# SmartCoffee.net
KiCad netlist of a schematic drawn in EAGLE
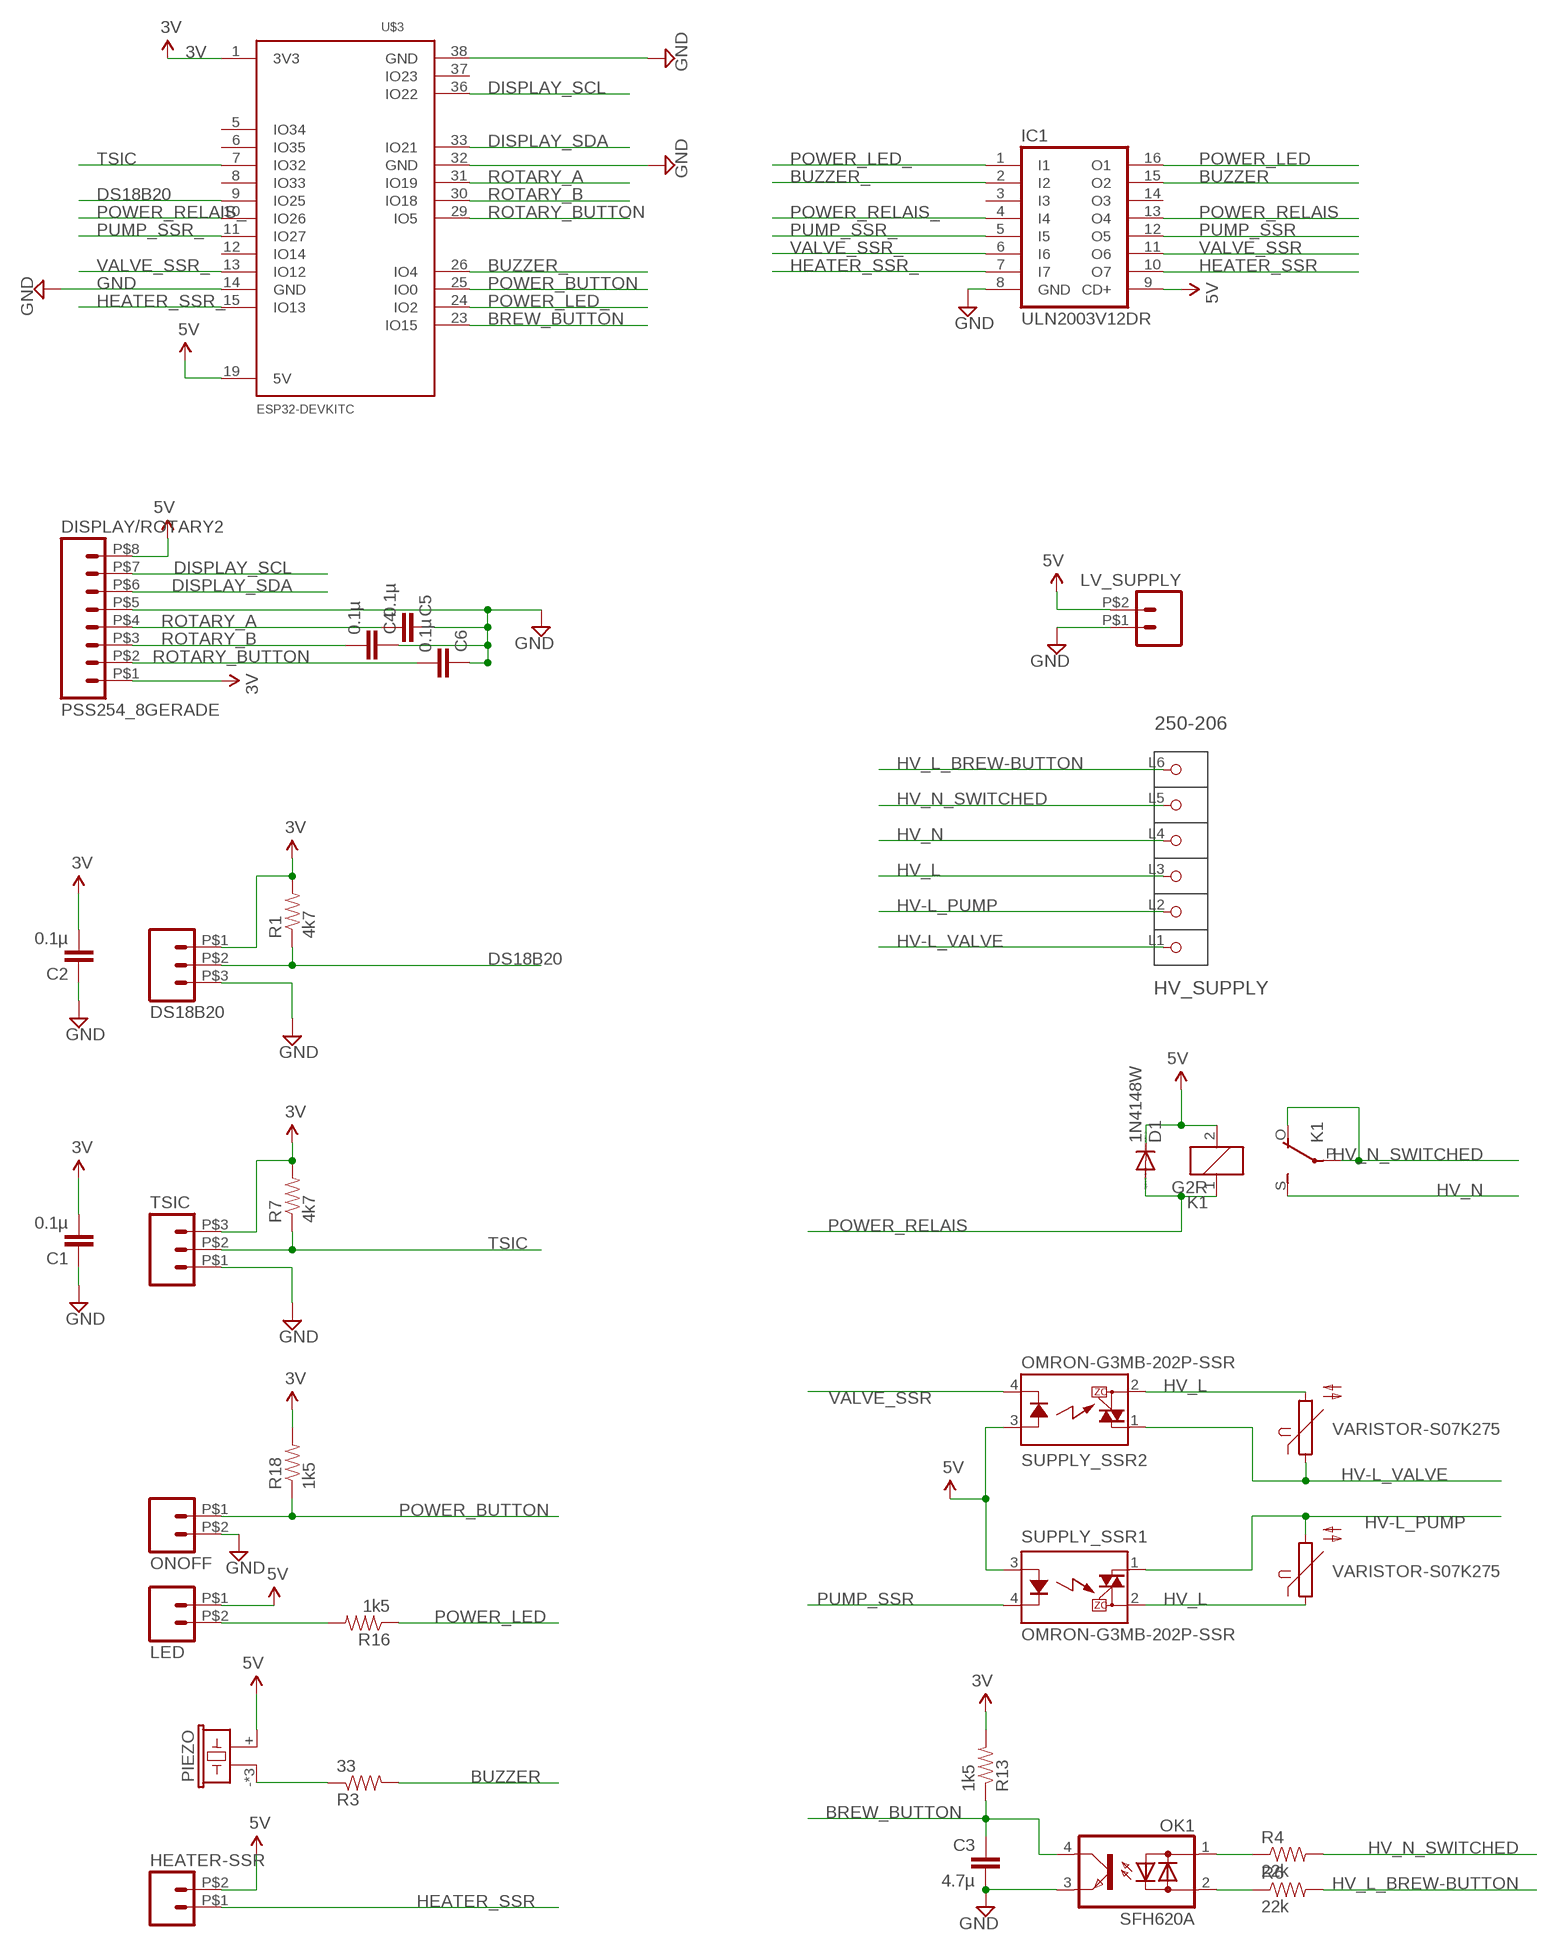
[diagram p0: schematic, sheet 1]

(export (version "E")
  (design (tool "Eeschema 10.0.6"))
  (components
    (comp (ref "C1")
      (value "0.1µ")
      (footprint "eagle-import:0603-CAP")
      (libsource (lib "eagle-import") (part "CAP0603-CAP"))
    )
    (comp (ref "C2")
      (value "0.1µ")
      (footprint "eagle-import:0603-CAP")
      (libsource (lib "eagle-import") (part "CAP0603-CAP"))
    )
    (comp (ref "C3")
      (value "4.7µ")
      (footprint "eagle-import:0805-CAP")
      (libsource (lib "eagle-import") (part "myLib_CAP0805-CAP"))
    )
    (comp (ref "C4")
      (value "0.1µ")
      (footprint "eagle-import:0603-CAP")
      (libsource (lib "eagle-import") (part "CAP0603-CAP"))
    )
    (comp (ref "C5")
      (value "0.1µ")
      (footprint "eagle-import:0603-CAP")
      (libsource (lib "eagle-import") (part "CAP0603-CAP"))
    )
    (comp (ref "C6")
      (value "0.1µ")
      (footprint "eagle-import:0603-CAP")
      (libsource (lib "eagle-import") (part "CAP0603-CAP"))
    )
    (comp (ref "D1")
      (value "1N4148W")
      (footprint "eagle-import:SOD123")
      (libsource (lib "eagle-import") (part "DIODE-SOD123"))
    )
    (comp (ref "DISPLAY/ROTARY2")
      (value "PSS254_8GERADE")
      (footprint "eagle-import:08G")
      (libsource (lib "eagle-import") (part "PSS254_8GERADE"))
    )
    (comp (ref "DS18B20")
      (value "PSS254_3GERADE")
      (footprint "eagle-import:03G")
      (libsource (lib "eagle-import") (part "PSS254_3GERADE"))
    )
    (comp (ref "HEATER-SSR")
      (value "PSS254_2GERADE")
      (footprint "eagle-import:02G")
      (libsource (lib "eagle-import") (part "PSS254_2GERADE"))
    )
    (comp (ref "HV_SUPPLY")
      (value "250-206")
      (footprint "eagle-import:P-250-206")
      (libsource (lib "eagle-import") (part "250-206"))
    )
    (comp (ref "IC1")
      (value "ULN2003V12DR")
      (footprint "eagle-import:SO16")
      (libsource (lib "eagle-import") (part "ULN2003AD"))
    )
    (comp (ref "K1")
      (value "G2R")
      (footprint "eagle-import:G2R")
      (libsource (lib "eagle-import") (part "G2R"))
    )
    (comp (ref "LED")
      (value "PSS254_2GERADE")
      (footprint "eagle-import:02G")
      (libsource (lib "eagle-import") (part "PSS254_2GERADE"))
    )
    (comp (ref "LV_SUPPLY")
      (value "PSS254_2GERADE")
      (footprint "eagle-import:02G")
      (libsource (lib "eagle-import") (part "PSS254_2GERADE"))
    )
    (comp (ref "OK1")
      (value "SFH620A")
      (footprint "eagle-import:DIL04")
      (fields (field (name "MPN") "SFH620A-2"))
      (libsource (lib "eagle-import") (part "SFH620A"))
    )
    (comp (ref "ONOFF")
      (value "PSS254_2GERADE")
      (footprint "eagle-import:02G")
      (libsource (lib "eagle-import") (part "PSS254_2GERADE"))
    )
    (comp (ref "PIEZO")
      (value "BUZZER-PIEZO_SMD")
      (footprint "eagle-import:BUZZER-PIEZO_SMD")
      (libsource (lib "eagle-import") (part "BUZZER-PIEZO_SMD"))
    )
    (comp (ref "R1")
      (value "4k7")
      (footprint "eagle-import:0603-RES")
      (libsource (lib "eagle-import") (part "RESISTOR0603-RES"))
    )
    (comp (ref "R3")
      (value "33")
      (footprint "eagle-import:0603-RES")
      (libsource (lib "eagle-import") (part "RESISTOR0603-RES"))
    )
    (comp (ref "R4")
      (value "22k")
      (footprint "eagle-import:RES_UPRIGHT")
      (libsource (lib "eagle-import") (part "myLib_RESISTORUPRIGHT"))
    )
    (comp (ref "R5")
      (value "VARISTOR-S07K275")
      (footprint "eagle-import:S07K275")
      (libsource (lib "eagle-import") (part "VARISTOR-S07K275"))
    )
    (comp (ref "R6")
      (value "22k")
      (footprint "eagle-import:RES_UPRIGHT")
      (libsource (lib "eagle-import") (part "myLib_RESISTORUPRIGHT"))
    )
    (comp (ref "R7")
      (value "4k7")
      (footprint "eagle-import:0603-RES")
      (libsource (lib "eagle-import") (part "RESISTOR0603-RES"))
    )
    (comp (ref "R8")
      (value "VARISTOR-S07K275")
      (footprint "eagle-import:S07K275")
      (libsource (lib "eagle-import") (part "VARISTOR-S07K275"))
    )
    (comp (ref "R13")
      (value "1k5")
      (footprint "eagle-import:0603-RES")
      (libsource (lib "eagle-import") (part "RESISTOR0603-RES"))
    )
    (comp (ref "R16")
      (value "1k5")
      (footprint "eagle-import:0603-RES")
      (libsource (lib "eagle-import") (part "RESISTOR0603-RES"))
    )
    (comp (ref "R18")
      (value "1k5")
      (footprint "eagle-import:0603-RES")
      (libsource (lib "eagle-import") (part "RESISTOR0603-RES"))
    )
    (comp (ref "SUPPLY_SSR1")
      (value "OMRON-G3MB-202P-SSR")
      (footprint "eagle-import:OMRON-G3MB-202P-SSR")
      (libsource (lib "eagle-import") (part "OMRON-G3MB-202P-SSR"))
    )
    (comp (ref "SUPPLY_SSR2")
      (value "OMRON-G3MB-202P-SSR")
      (footprint "eagle-import:OMRON-G3MB-202P-SSR")
      (libsource (lib "eagle-import") (part "OMRON-G3MB-202P-SSR"))
    )
    (comp (ref "TSIC")
      (value "PSS254_3GERADE")
      (footprint "eagle-import:03G")
      (libsource (lib "eagle-import") (part "PSS254_3GERADE"))
    )
    (comp (ref "U$3")
      (value "ESP32DEVKITC")
      (footprint "eagle-import:ESP32-DEVKITC")
      (libsource (lib "eagle-import") (part "ESP32DEVKITC"))
    )
  )
  (nets
    (net (code "1") (name "/BREW_BUTTON") (class "Default")
      (node (ref "C3") (pin "1") (pinfunction "1_1") (pintype "passive"))
      (node (ref "OK1") (pin "4") (pinfunction "C_4") (pintype "passive"))
      (node (ref "R13") (pin "1") (pinfunction "1_1") (pintype "passive"))
      (node (ref "U$3") (pin "23") (pinfunction "IO15_23") (pintype "bidirectional"))
    )
    (net (code "2") (name "/BUZZER") (class "Default")
      (node (ref "IC1") (pin "15") (pinfunction "O2_15") (pintype "open_collector"))
      (node (ref "R3") (pin "2") (pinfunction "2_2") (pintype "passive"))
    )
    (net (code "3") (name "/BUZZER_") (class "Default")
      (node (ref "IC1") (pin "2") (pinfunction "I2_2") (pintype "input"))
      (node (ref "U$3") (pin "26") (pinfunction "IO4_26") (pintype "bidirectional"))
    )
    (net (code "4") (name "/DISPLAY_SCL") (class "Default")
      (node (ref "DISPLAY/ROTARY2") (pin "P$7") (pinfunction "7_P$7") (pintype "passive"))
      (node (ref "U$3") (pin "36") (pinfunction "IO22_36") (pintype "bidirectional"))
    )
    (net (code "5") (name "/DISPLAY_SDA") (class "Default")
      (node (ref "DISPLAY/ROTARY2") (pin "P$6") (pinfunction "6_P$6") (pintype "passive"))
      (node (ref "U$3") (pin "33") (pinfunction "IO21_33") (pintype "bidirectional"))
    )
    (net (code "6") (name "/DS18B20") (class "Default")
      (node (ref "DS18B20") (pin "P$2") (pinfunction "2_P$2") (pintype "passive"))
      (node (ref "R1") (pin "1") (pinfunction "1_1") (pintype "passive"))
      (node (ref "U$3") (pin "9") (pinfunction "IO25_9") (pintype "bidirectional"))
    )
    (net (code "7") (name "/HEATER_SSR") (class "Default")
      (node (ref "HEATER-SSR") (pin "P$1") (pinfunction "1_P$1") (pintype "passive"))
      (node (ref "IC1") (pin "10") (pinfunction "O7_10") (pintype "open_collector"))
    )
    (net (code "8") (name "/HEATER_SSR_") (class "Default")
      (node (ref "IC1") (pin "7") (pinfunction "I7_7") (pintype "input"))
      (node (ref "U$3") (pin "15") (pinfunction "IO13_15") (pintype "bidirectional"))
    )
    (net (code "9") (name "/HV-L_PUMP") (class "Default")
      (node (ref "HV_SUPPLY") (pin "L2") (pinfunction "P2_L2") (pintype "bidirectional"))
      (node (ref "R8") (pin "2") (pinfunction "2_2") (pintype "passive"))
      (node (ref "SUPPLY_SSR1") (pin "1") (pinfunction "DS1_1") (pintype "passive"))
    )
    (net (code "10") (name "/HV-L_VALVE") (class "Default")
      (node (ref "HV_SUPPLY") (pin "L1") (pinfunction "P1_L1") (pintype "bidirectional"))
      (node (ref "R5") (pin "1") (pinfunction "1_1") (pintype "passive"))
      (node (ref "SUPPLY_SSR2") (pin "1") (pinfunction "DS1_1") (pintype "passive"))
    )
    (net (code "11") (name "/HV_L") (class "Default")
      (node (ref "HV_SUPPLY") (pin "L3") (pinfunction "P3_L3") (pintype "bidirectional"))
      (node (ref "R5") (pin "2") (pinfunction "2_2") (pintype "passive"))
      (node (ref "R8") (pin "1") (pinfunction "1_1") (pintype "passive"))
      (node (ref "SUPPLY_SSR1") (pin "2") (pinfunction "DS2_2") (pintype "passive"))
      (node (ref "SUPPLY_SSR2") (pin "2") (pinfunction "DS2_2") (pintype "passive"))
    )
    (net (code "12") (name "/HV_L_BREW-BUTTON") (class "Default")
      (node (ref "HV_SUPPLY") (pin "L6") (pinfunction "P6_L6") (pintype "bidirectional"))
      (node (ref "R6") (pin "2") (pinfunction "2_2") (pintype "passive"))
    )
    (net (code "13") (name "/HV_N") (class "Default")
      (node (ref "HV_SUPPLY") (pin "L4") (pinfunction "P4_L4") (pintype "bidirectional"))
      (node (ref "K1") (pin "S") (pinfunction "S_S") (pintype "passive"))
    )
    (net (code "14") (name "/HV_N_SWITCHED") (class "Default")
      (node (ref "HV_SUPPLY") (pin "L5") (pinfunction "P5_L5") (pintype "bidirectional"))
      (node (ref "K1") (pin "O") (pinfunction "O_O") (pintype "passive"))
      (node (ref "K1") (pin "P") (pinfunction "P_P") (pintype "passive"))
      (node (ref "R4") (pin "2") (pinfunction "2_2") (pintype "passive"))
    )
    (net (code "15") (name "/POWER_BUTTON") (class "Default")
      (node (ref "ONOFF") (pin "P$1") (pinfunction "1_P$1") (pintype "passive"))
      (node (ref "R18") (pin "1") (pinfunction "1_1") (pintype "passive"))
      (node (ref "U$3") (pin "25") (pinfunction "IO0_25") (pintype "bidirectional"))
    )
    (net (code "16") (name "/POWER_LED") (class "Default")
      (node (ref "IC1") (pin "16") (pinfunction "O1_16") (pintype "open_collector"))
      (node (ref "R16") (pin "1") (pinfunction "1_1") (pintype "passive"))
    )
    (net (code "17") (name "/POWER_LED_") (class "Default")
      (node (ref "IC1") (pin "1") (pinfunction "I1_1") (pintype "input"))
      (node (ref "U$3") (pin "24") (pinfunction "IO2_24") (pintype "bidirectional"))
    )
    (net (code "18") (name "/POWER_RELAIS") (class "Default")
      (node (ref "D1") (pin "A") (pinfunction "A_A") (pintype "passive"))
      (node (ref "IC1") (pin "13") (pinfunction "O4_13") (pintype "open_collector"))
      (node (ref "K1") (pin "1") (pinfunction "1_1") (pintype "passive"))
    )
    (net (code "19") (name "/POWER_RELAIS_") (class "Default")
      (node (ref "IC1") (pin "4") (pinfunction "I4_4") (pintype "input"))
      (node (ref "U$3") (pin "10") (pinfunction "IO26_10") (pintype "bidirectional"))
    )
    (net (code "20") (name "/PUMP_SSR") (class "Default")
      (node (ref "IC1") (pin "12") (pinfunction "O5_12") (pintype "open_collector"))
      (node (ref "SUPPLY_SSR1") (pin "4") (pinfunction "K_4") (pintype "passive"))
    )
    (net (code "21") (name "/PUMP_SSR_") (class "Default")
      (node (ref "IC1") (pin "5") (pinfunction "I5_5") (pintype "input"))
      (node (ref "U$3") (pin "11") (pinfunction "IO27_11") (pintype "bidirectional"))
    )
    (net (code "22") (name "/ROTARY_A") (class "Default")
      (node (ref "C5") (pin "2") (pinfunction "2_2") (pintype "passive"))
      (node (ref "DISPLAY/ROTARY2") (pin "P$4") (pinfunction "4_P$4") (pintype "passive"))
      (node (ref "U$3") (pin "31") (pinfunction "IO19_31") (pintype "bidirectional"))
    )
    (net (code "23") (name "/ROTARY_B") (class "Default")
      (node (ref "C4") (pin "2") (pinfunction "2_2") (pintype "passive"))
      (node (ref "DISPLAY/ROTARY2") (pin "P$3") (pinfunction "3_P$3") (pintype "passive"))
      (node (ref "U$3") (pin "30") (pinfunction "IO18_30") (pintype "bidirectional"))
    )
    (net (code "24") (name "/ROTARY_BUTTON") (class "Default")
      (node (ref "C6") (pin "2") (pinfunction "2_2") (pintype "passive"))
      (node (ref "DISPLAY/ROTARY2") (pin "P$2") (pinfunction "2_P$2") (pintype "passive"))
      (node (ref "U$3") (pin "29") (pinfunction "IO5_29") (pintype "bidirectional"))
    )
    (net (code "25") (name "/TSIC") (class "Default")
      (node (ref "R7") (pin "1") (pinfunction "1_1") (pintype "passive"))
      (node (ref "TSIC") (pin "P$2") (pinfunction "2_P$2") (pintype "passive"))
      (node (ref "U$3") (pin "7") (pinfunction "IO32_7") (pintype "bidirectional"))
    )
    (net (code "26") (name "/VALVE_SSR") (class "Default")
      (node (ref "IC1") (pin "11") (pinfunction "O6_11") (pintype "open_collector"))
      (node (ref "SUPPLY_SSR2") (pin "4") (pinfunction "K_4") (pintype "passive"))
    )
    (net (code "27") (name "/VALVE_SSR_") (class "Default")
      (node (ref "IC1") (pin "6") (pinfunction "I6_6") (pintype "input"))
      (node (ref "U$3") (pin "13") (pinfunction "IO12_13") (pintype "bidirectional"))
    )
    (net (code "28") (name "3V") (class "Default")
      (node (ref "C1") (pin "2") (pinfunction "2_2") (pintype "passive"))
      (node (ref "C2") (pin "2") (pinfunction "2_2") (pintype "passive"))
      (node (ref "DISPLAY/ROTARY2") (pin "P$1") (pinfunction "1_P$1") (pintype "passive"))
      (node (ref "DS18B20") (pin "P$1") (pinfunction "1_P$1") (pintype "passive"))
      (node (ref "R1") (pin "2") (pinfunction "2_2") (pintype "passive"))
      (node (ref "R13") (pin "2") (pinfunction "2_2") (pintype "passive"))
      (node (ref "R18") (pin "2") (pinfunction "2_2") (pintype "passive"))
      (node (ref "R7") (pin "2") (pinfunction "2_2") (pintype "passive"))
      (node (ref "TSIC") (pin "P$3") (pinfunction "3_P$3") (pintype "passive"))
      (node (ref "U$3") (pin "1") (pinfunction "3V3_1") (pintype "bidirectional"))
    )
    (net (code "29") (name "5V") (class "Default")
      (node (ref "D1") (pin "C") (pinfunction "C_C") (pintype "passive"))
      (node (ref "DISPLAY/ROTARY2") (pin "P$8") (pinfunction "8_P$8") (pintype "passive"))
      (node (ref "HEATER-SSR") (pin "P$2") (pinfunction "2_P$2") (pintype "passive"))
      (node (ref "IC1") (pin "9") (pinfunction "CD+_9") (pintype "passive"))
      (node (ref "K1") (pin "2") (pinfunction "2_2") (pintype "passive"))
      (node (ref "LED") (pin "P$1") (pinfunction "1_P$1") (pintype "passive"))
      (node (ref "LV_SUPPLY") (pin "P$2") (pinfunction "2_P$2") (pintype "passive"))
      (node (ref "PIEZO") (pin "+") (pinfunction "1_+") (pintype "passive"))
      (node (ref "SUPPLY_SSR1") (pin "3") (pinfunction "A_3") (pintype "passive"))
      (node (ref "SUPPLY_SSR2") (pin "3") (pinfunction "A_3") (pintype "passive"))
      (node (ref "U$3") (pin "19") (pinfunction "5V_19") (pintype "bidirectional"))
    )
    (net (code "30") (name "GND") (class "Default")
      (node (ref "C1") (pin "1") (pinfunction "1_1") (pintype "passive"))
      (node (ref "C2") (pin "1") (pinfunction "1_1") (pintype "passive"))
      (node (ref "C3") (pin "2") (pinfunction "2_2") (pintype "passive"))
      (node (ref "C4") (pin "1") (pinfunction "1_1") (pintype "passive"))
      (node (ref "C5") (pin "1") (pinfunction "1_1") (pintype "passive"))
      (node (ref "C6") (pin "1") (pinfunction "1_1") (pintype "passive"))
      (node (ref "DISPLAY/ROTARY2") (pin "P$5") (pinfunction "5_P$5") (pintype "passive"))
      (node (ref "DS18B20") (pin "P$3") (pinfunction "3_P$3") (pintype "passive"))
      (node (ref "IC1") (pin "8") (pinfunction "GND_8") (pintype "power_in"))
      (node (ref "LV_SUPPLY") (pin "P$1") (pinfunction "1_P$1") (pintype "passive"))
      (node (ref "OK1") (pin "3") (pinfunction "E_3") (pintype "passive"))
      (node (ref "ONOFF") (pin "P$2") (pinfunction "2_P$2") (pintype "passive"))
      (node (ref "TSIC") (pin "P$1") (pinfunction "1_P$1") (pintype "passive"))
      (node (ref "U$3") (pin "14") (pinfunction "GND_14") (pintype "bidirectional"))
      (node (ref "U$3") (pin "32") (pinfunction "GND_32") (pintype "bidirectional"))
      (node (ref "U$3") (pin "38") (pinfunction "GND_38") (pintype "bidirectional"))
    )
    (net (code "31") (name "Net-(LED-2)") (class "Default")
      (node (ref "LED") (pin "P$2") (pinfunction "2_P$2") (pintype "passive"))
      (node (ref "R16") (pin "2") (pinfunction "2_2") (pintype "passive"))
    )
    (net (code "32") (name "Net-(OK1-AC1)") (class "Default")
      (node (ref "OK1") (pin "1") (pinfunction "AC1_1") (pintype "passive"))
      (node (ref "R4") (pin "1") (pinfunction "1_1") (pintype "passive"))
    )
    (net (code "33") (name "Net-(OK1-AC2)") (class "Default")
      (node (ref "OK1") (pin "2") (pinfunction "AC2_2") (pintype "passive"))
      (node (ref "R6") (pin "1") (pinfunction "1_1") (pintype "passive"))
    )
    (net (code "34") (name "Net-(PIEZO-2-Pad-)") (class "Default")
      (node (ref "PIEZO") (pin "-") (pinfunction "2_-") (pintype "passive"))
      (node (ref "PIEZO") (pin "DUMMY") (pinfunction "2_DUMMY") (pintype "passive"))
      (node (ref "PIEZO") (pin "DUMMY1") (pinfunction "2_DUMMY1") (pintype "passive"))
      (node (ref "R3") (pin "1") (pinfunction "1_1") (pintype "passive"))
    )
    (net (code "35") (name "unconnected-(IC1-I3-Pad3)") (class "Default")
      (node (ref "IC1") (pin "3") (pinfunction "I3_3") (pintype "input"))
    )
    (net (code "36") (name "unconnected-(IC1-O3-Pad14)") (class "Default")
      (node (ref "IC1") (pin "14") (pinfunction "O3_14") (pintype "open_collector"))
    )
    (net (code "37") (name "unconnected-(U$3-IO14-Pad12)") (class "Default")
      (node (ref "U$3") (pin "12") (pinfunction "IO14_12") (pintype "bidirectional"))
    )
    (net (code "38") (name "unconnected-(U$3-IO23-Pad37)") (class "Default")
      (node (ref "U$3") (pin "37") (pinfunction "IO23_37") (pintype "bidirectional"))
    )
    (net (code "39") (name "unconnected-(U$3-IO33-Pad8)") (class "Default")
      (node (ref "U$3") (pin "8") (pinfunction "IO33_8") (pintype "bidirectional"))
    )
    (net (code "40") (name "unconnected-(U$3-IO34-Pad5)") (class "Default")
      (node (ref "U$3") (pin "5") (pinfunction "IO34_5") (pintype "bidirectional"))
    )
    (net (code "41") (name "unconnected-(U$3-IO35-Pad6)") (class "Default")
      (node (ref "U$3") (pin "6") (pinfunction "IO35_6") (pintype "bidirectional"))
    )
  )
)
